# ridicideska.net
KiCad netlist of a schematic drawn in EAGLE
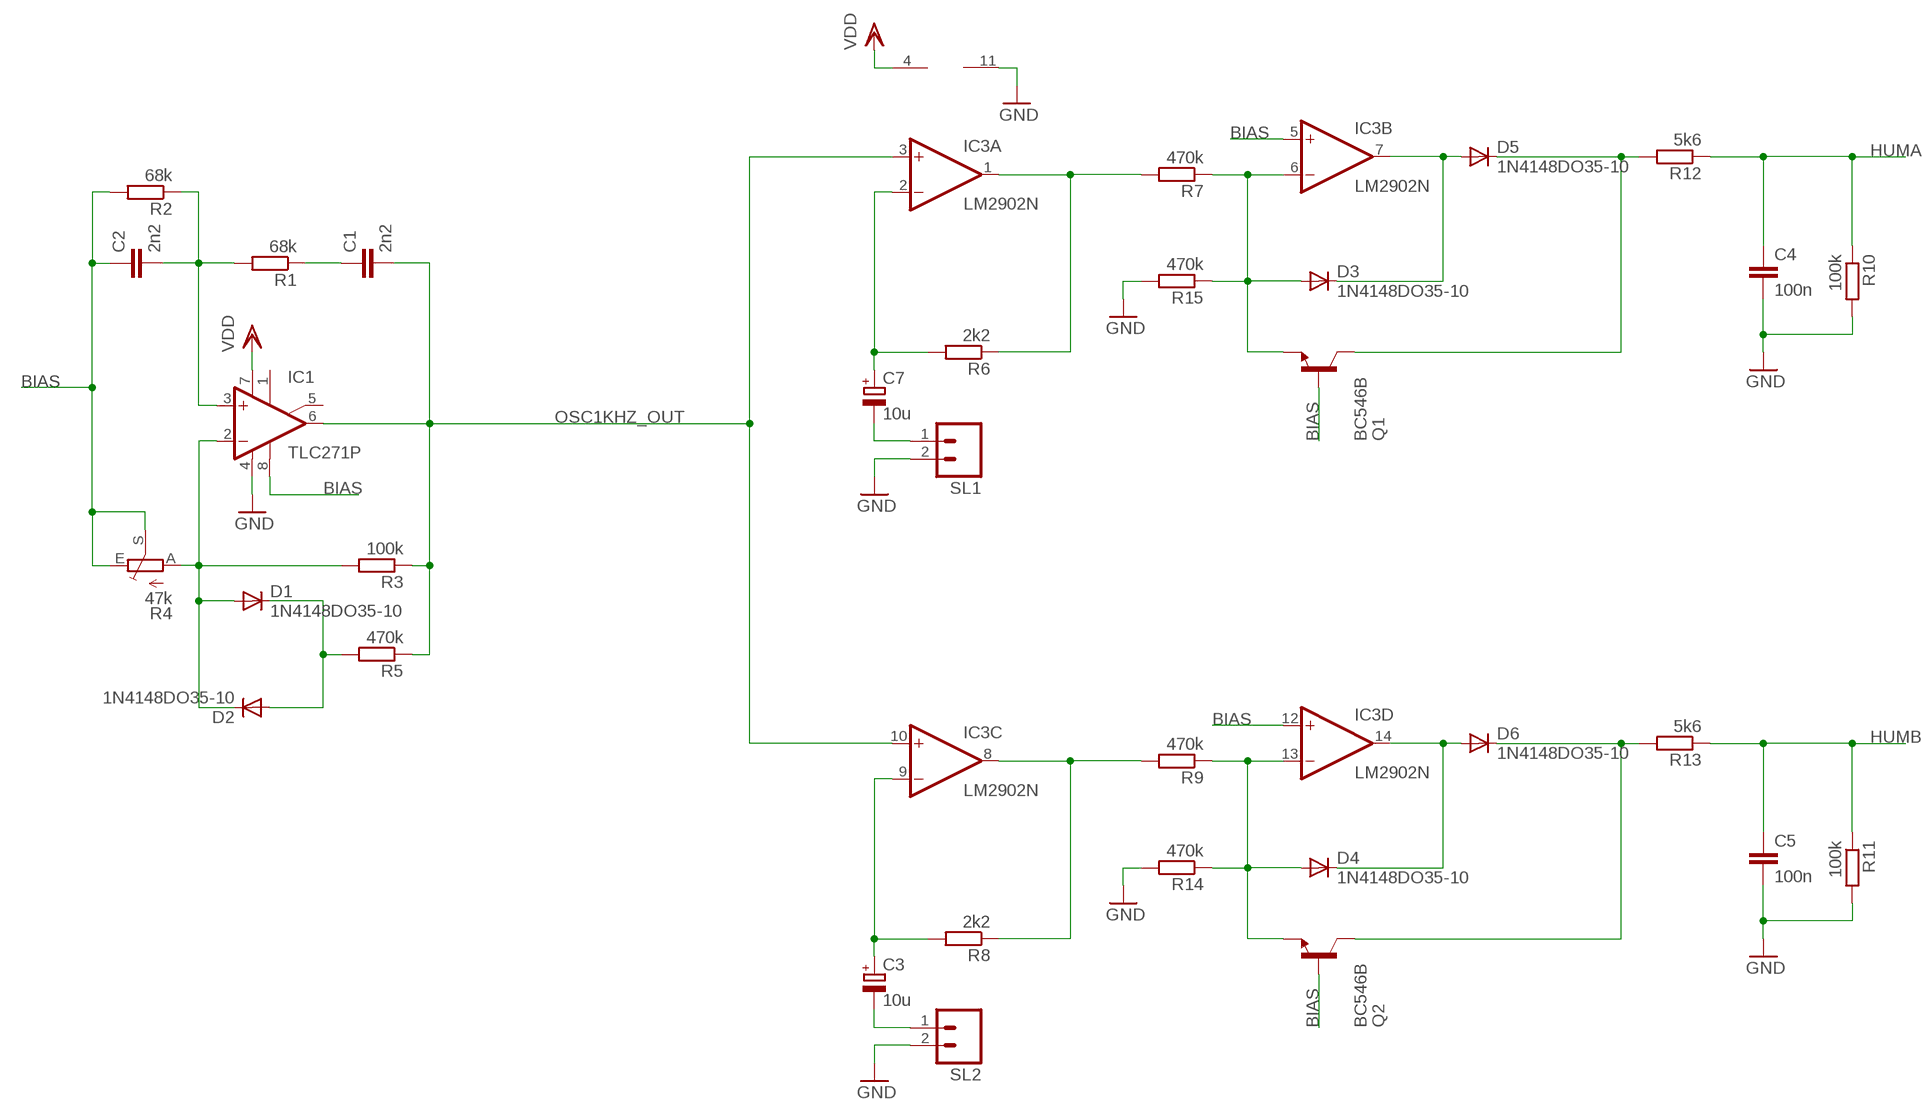
[diagram p0: schematic, sheet 1]
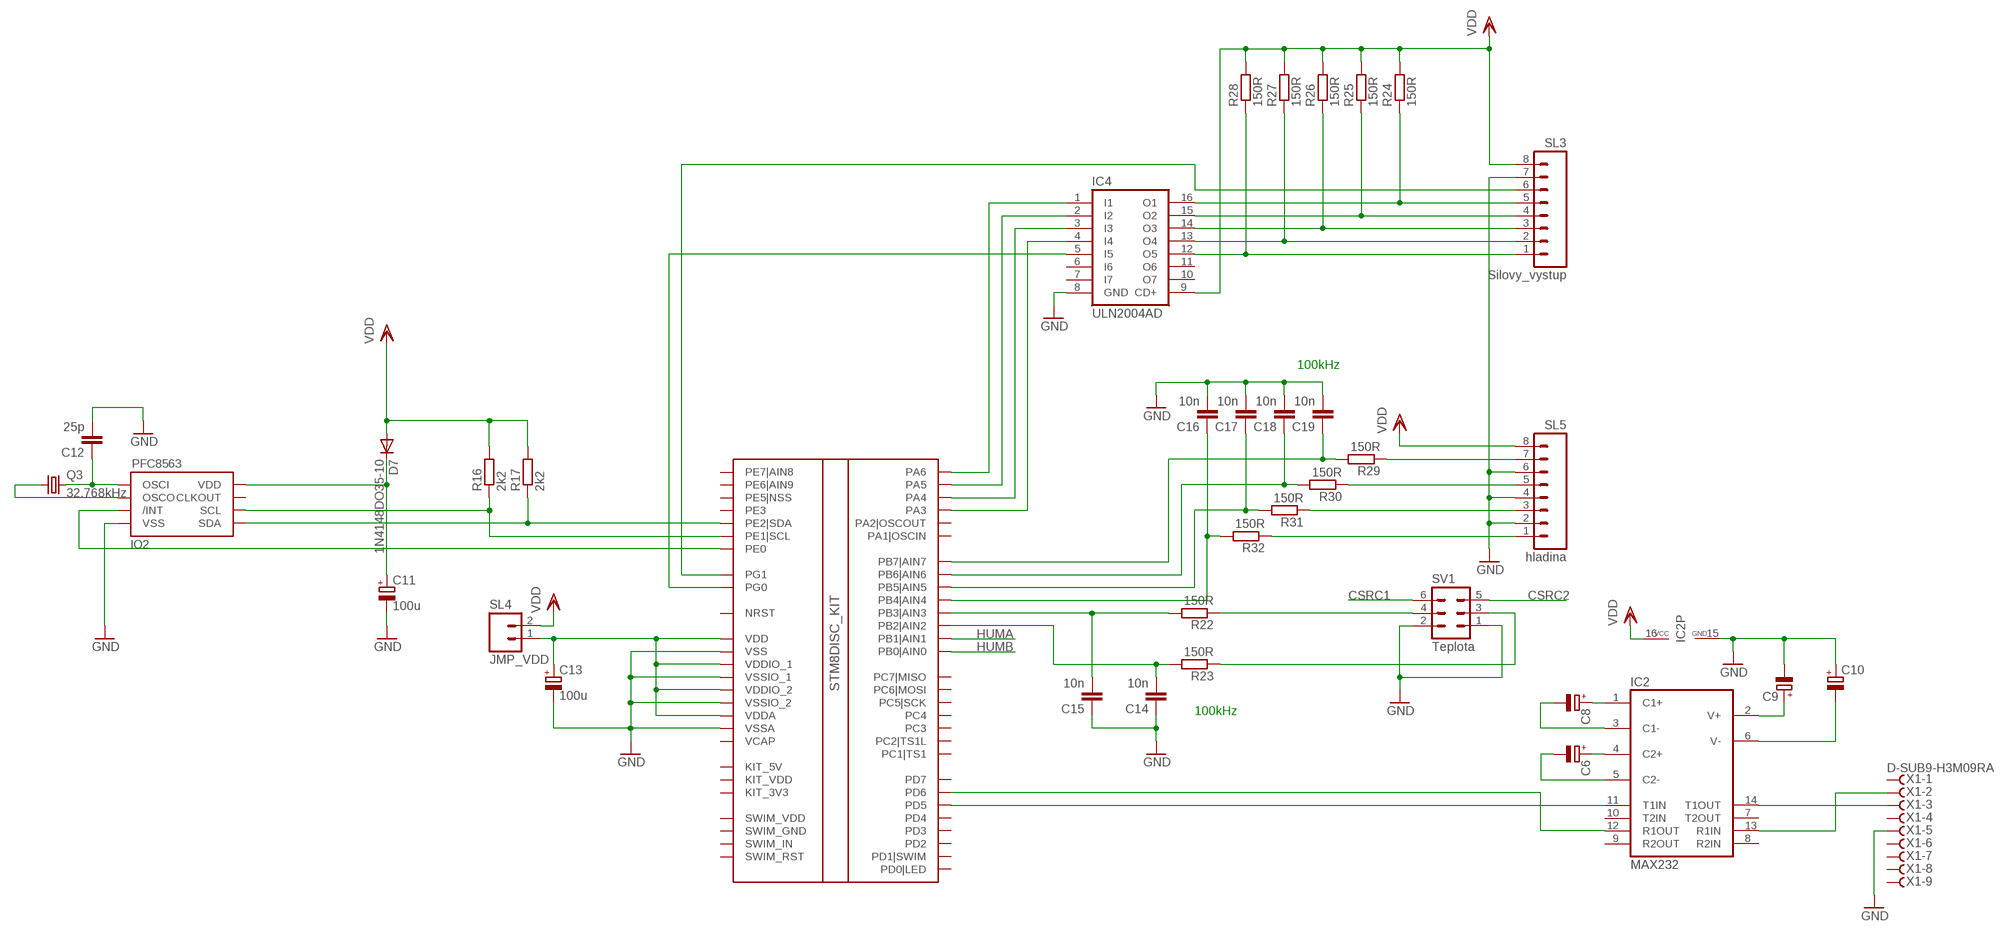
[diagram p1: schematic, sheet 2]
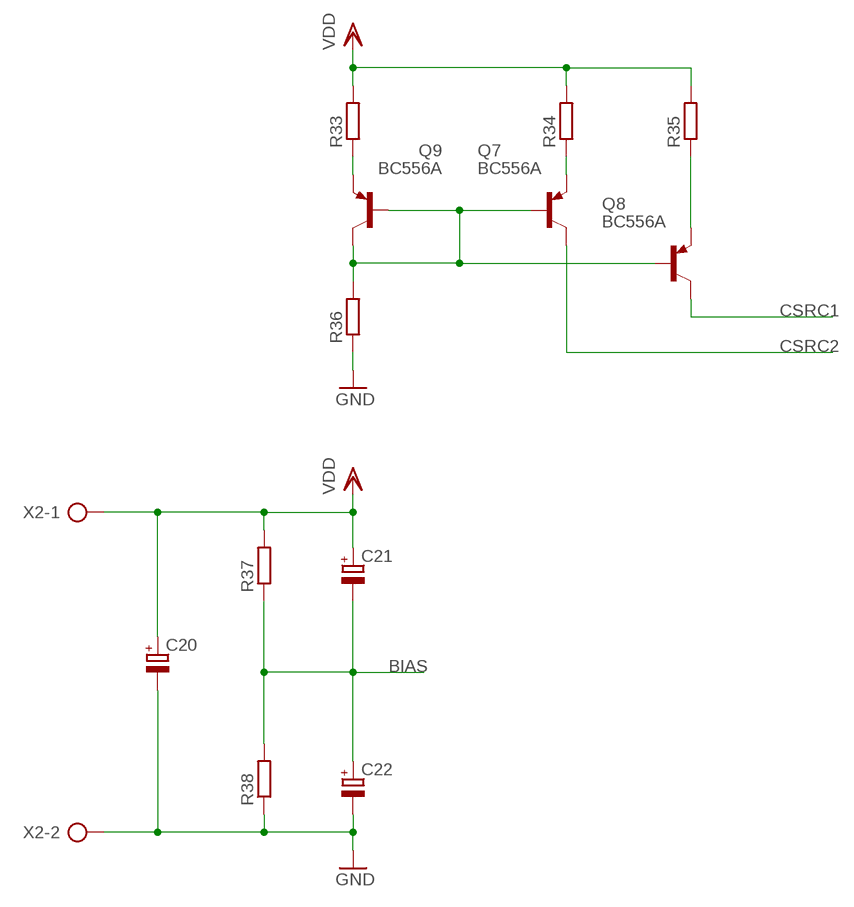
[diagram p2: schematic, sheet 3]

(export (version "E")
  (design (tool "Eeschema 10.0.6"))
  (components
    (comp (ref "C20")
      (value "CPOL-EUE5-10.5")
      (footprint "eagle-import:E5-10,5")
      (libsource (lib "eagle-import") (part "resistor_CPOL-EUE5-10.5"))
    )
    (comp (ref "C21")
      (value "CPOL-EUE5-10.5")
      (footprint "eagle-import:E5-10,5")
      (libsource (lib "eagle-import") (part "resistor_CPOL-EUE5-10.5"))
    )
    (comp (ref "C22")
      (value "CPOL-EUE5-10.5")
      (footprint "eagle-import:E5-10,5")
      (libsource (lib "eagle-import") (part "resistor_CPOL-EUE5-10.5"))
    )
    (comp (ref "Q7")
      (value "BC556A")
      (footprint "eagle-import:TO92-EBC")
      (libsource (lib "eagle-import") (part "BC556A"))
    )
    (comp (ref "Q8")
      (value "BC556A")
      (footprint "eagle-import:TO92-EBC")
      (libsource (lib "eagle-import") (part "BC556A"))
    )
    (comp (ref "Q9")
      (value "BC556A")
      (footprint "eagle-import:TO92-EBC")
      (libsource (lib "eagle-import") (part "BC556A"))
    )
    (comp (ref "R33")
      (value "R-EU_R0805")
      (footprint "eagle-import:R0805")
      (libsource (lib "eagle-import") (part "R-EU_R0805"))
    )
    (comp (ref "R34")
      (value "R-EU_R0805")
      (footprint "eagle-import:R0805")
      (libsource (lib "eagle-import") (part "R-EU_R0805"))
    )
    (comp (ref "R35")
      (value "R-EU_R0805")
      (footprint "eagle-import:R0805")
      (libsource (lib "eagle-import") (part "R-EU_R0805"))
    )
    (comp (ref "R36")
      (value "R-EU_R0805")
      (footprint "eagle-import:R0805")
      (libsource (lib "eagle-import") (part "R-EU_R0805"))
    )
    (comp (ref "R37")
      (value "R-EU_0207/12")
      (footprint "eagle-import:0207_12")
      (libsource (lib "eagle-import") (part "resistor_R-EU_0207/12"))
    )
    (comp (ref "R38")
      (value "R-EU_0207/12")
      (footprint "eagle-import:0207_12")
      (libsource (lib "eagle-import") (part "resistor_R-EU_0207/12"))
    )
    (comp (ref "X2")
      (value "AK300/2")
      (footprint "eagle-import:AK300_2")
      (libsource (lib "eagle-import") (part "AK300/2"))
    )
    (comp (ref "C6")
      (value "CPOL-EUE5-10.5")
      (footprint "eagle-import:E5-10,5")
      (libsource (lib "eagle-import") (part "resistor_CPOL-EUE5-10.5"))
    )
    (comp (ref "C8")
      (value "CPOL-EUE5-10.5")
      (footprint "eagle-import:E5-10,5")
      (libsource (lib "eagle-import") (part "resistor_CPOL-EUE5-10.5"))
    )
    (comp (ref "C9")
      (value "CPOL-EUE5-10.5")
      (footprint "eagle-import:E5-10,5")
      (libsource (lib "eagle-import") (part "resistor_CPOL-EUE5-10.5"))
    )
    (comp (ref "C10")
      (value "CPOL-EUE5-10.5")
      (footprint "eagle-import:E5-10,5")
      (libsource (lib "eagle-import") (part "resistor_CPOL-EUE5-10.5"))
    )
    (comp (ref "C11")
      (value "100u")
      (footprint "eagle-import:E5-10,5")
      (libsource (lib "eagle-import") (part "resistor_CPOL-EUE5-10.5"))
    )
    (comp (ref "C12")
      (value "25p")
      (footprint "eagle-import:C0805")
      (libsource (lib "eagle-import") (part "C-EUC0805"))
    )
    (comp (ref "C13")
      (value "100u")
      (footprint "eagle-import:E5-10,5")
      (libsource (lib "eagle-import") (part "resistor_CPOL-EUE5-10.5"))
    )
    (comp (ref "C14")
      (value "10n")
      (footprint "eagle-import:C0805")
      (libsource (lib "eagle-import") (part "C-EUC0805"))
    )
    (comp (ref "C15")
      (value "10n")
      (footprint "eagle-import:C0805")
      (libsource (lib "eagle-import") (part "C-EUC0805"))
    )
    (comp (ref "C16")
      (value "10n")
      (footprint "eagle-import:C0805")
      (libsource (lib "eagle-import") (part "C-EUC0805"))
    )
    (comp (ref "C17")
      (value "10n")
      (footprint "eagle-import:C0805")
      (libsource (lib "eagle-import") (part "C-EUC0805"))
    )
    (comp (ref "C18")
      (value "10n")
      (footprint "eagle-import:C0805")
      (libsource (lib "eagle-import") (part "C-EUC0805"))
    )
    (comp (ref "C19")
      (value "10n")
      (footprint "eagle-import:C0805")
      (libsource (lib "eagle-import") (part "C-EUC0805"))
    )
    (comp (ref "D7")
      (value "1N4148DO35-10")
      (footprint "eagle-import:DO35-10")
      (libsource (lib "eagle-import") (part "1N4148DO35-10"))
    )
    (comp (ref "IC2")
      (value "MAX232")
      (footprint "eagle-import:DIL16")
      (fields (field (name "MF") "MAXIM") (field (name "MPN") "MAX232ACPE+"))
      (libsource (lib "eagle-import") (part "MAX232"))
    )
    (comp (ref "IC4")
      (value "ULN2004AD")
      (footprint "eagle-import:SO16")
      (libsource (lib "eagle-import") (part "ULN2004AD"))
    )
    (comp (ref "IO1")
      (value "STM8_KIT")
      (footprint "eagle-import:STM8SDISCOVERY")
      (libsource (lib "eagle-import") (part "STM8_KIT"))
    )
    (comp (ref "IO2")
      (value "PFC8563")
      (footprint "eagle-import:SO08")
      (libsource (lib "eagle-import") (part "PFC8563"))
    )
    (comp (ref "Q3")
      (value "32.768kHz")
      (footprint "eagle-import:HC49U70")
      (libsource (lib "eagle-import") (part "CRYSTALHC49U70"))
    )
    (comp (ref "R16")
      (value "2k2")
      (footprint "eagle-import:0207_12")
      (libsource (lib "eagle-import") (part "R-EU_0207/12"))
    )
    (comp (ref "R17")
      (value "2k2")
      (footprint "eagle-import:0207_12")
      (libsource (lib "eagle-import") (part "R-EU_0207/12"))
    )
    (comp (ref "R22")
      (value "150R")
      (footprint "eagle-import:R0805")
      (libsource (lib "eagle-import") (part "R-EU_R0805"))
    )
    (comp (ref "R23")
      (value "150R")
      (footprint "eagle-import:R0805")
      (libsource (lib "eagle-import") (part "R-EU_R0805"))
    )
    (comp (ref "R24")
      (value "150R")
      (footprint "eagle-import:0207_12")
      (libsource (lib "eagle-import") (part "R-EU_0207/12"))
    )
    (comp (ref "R25")
      (value "150R")
      (footprint "eagle-import:0207_12")
      (libsource (lib "eagle-import") (part "R-EU_0207/12"))
    )
    (comp (ref "R26")
      (value "150R")
      (footprint "eagle-import:0207_12")
      (libsource (lib "eagle-import") (part "R-EU_0207/12"))
    )
    (comp (ref "R27")
      (value "150R")
      (footprint "eagle-import:0207_12")
      (libsource (lib "eagle-import") (part "R-EU_0207/12"))
    )
    (comp (ref "R28")
      (value "150R")
      (footprint "eagle-import:0207_12")
      (libsource (lib "eagle-import") (part "R-EU_0207/12"))
    )
    (comp (ref "R29")
      (value "150R")
      (footprint "eagle-import:R0805")
      (libsource (lib "eagle-import") (part "R-EU_R0805"))
    )
    (comp (ref "R30")
      (value "150R")
      (footprint "eagle-import:R0805")
      (libsource (lib "eagle-import") (part "R-EU_R0805"))
    )
    (comp (ref "R31")
      (value "150R")
      (footprint "eagle-import:R0805")
      (libsource (lib "eagle-import") (part "R-EU_R0805"))
    )
    (comp (ref "R32")
      (value "150R")
      (footprint "eagle-import:R0805")
      (libsource (lib "eagle-import") (part "R-EU_R0805"))
    )
    (comp (ref "SL3")
      (value "Silovy_vystup")
      (footprint "eagle-import:08P")
      (libsource (lib "eagle-import") (part "M08"))
    )
    (comp (ref "SL4")
      (value "JMP_VDD")
      (footprint "eagle-import:02P")
      (libsource (lib "eagle-import") (part "M02"))
    )
    (comp (ref "SL5")
      (value "hladina")
      (footprint "eagle-import:08P")
      (fields (field (name "OC_FARNELL") "unknown") (field (name "OC_NEWARK") "unknown"))
      (libsource (lib "eagle-import") (part "M08"))
    )
    (comp (ref "SV1")
      (value "Teplota")
      (footprint "eagle-import:MA03-2")
      (libsource (lib "eagle-import") (part "MA03-2"))
    )
    (comp (ref "X1")
      (value "D-SUB9-H3M09RA")
      (footprint "eagle-import:H3M09RA")
      (libsource (lib "eagle-import") (part "D-SUB9-H3M09RA"))
    )
    (comp (ref "C1")
      (value "2n2")
      (footprint "eagle-import:C0805")
      (libsource (lib "eagle-import") (part "C-EUC0805"))
    )
    (comp (ref "C2")
      (value "2n2")
      (footprint "eagle-import:C0805")
      (libsource (lib "eagle-import") (part "C-EUC0805"))
    )
    (comp (ref "C3")
      (value "10u")
      (footprint "eagle-import:E5-13")
      (libsource (lib "eagle-import") (part "CPOL-EUE5-13"))
    )
    (comp (ref "C4")
      (value "100n")
      (footprint "eagle-import:C0805")
      (libsource (lib "eagle-import") (part "C-EUC0805"))
    )
    (comp (ref "C5")
      (value "100n")
      (footprint "eagle-import:C0805")
      (libsource (lib "eagle-import") (part "C-EUC0805"))
    )
    (comp (ref "C7")
      (value "10u")
      (footprint "eagle-import:E5-13")
      (libsource (lib "eagle-import") (part "CPOL-EUE5-13"))
    )
    (comp (ref "D1")
      (value "1N4148DO35-10")
      (footprint "eagle-import:DO35-10")
      (libsource (lib "eagle-import") (part "1N4148DO35-10"))
    )
    (comp (ref "D2")
      (value "1N4148DO35-10")
      (footprint "eagle-import:DO35-10")
      (libsource (lib "eagle-import") (part "1N4148DO35-10"))
    )
    (comp (ref "D3")
      (value "1N4148DO35-10")
      (footprint "eagle-import:DO35-10")
      (libsource (lib "eagle-import") (part "1N4148DO35-10"))
    )
    (comp (ref "D4")
      (value "1N4148DO35-10")
      (footprint "eagle-import:DO35-10")
      (libsource (lib "eagle-import") (part "1N4148DO35-10"))
    )
    (comp (ref "D5")
      (value "1N4148DO35-10")
      (footprint "eagle-import:DO35-10")
      (libsource (lib "eagle-import") (part "1N4148DO35-10"))
    )
    (comp (ref "D6")
      (value "1N4148DO35-10")
      (footprint "eagle-import:DO35-10")
      (libsource (lib "eagle-import") (part "1N4148DO35-10"))
    )
    (comp (ref "IC1")
      (value "TLC271P")
      (footprint "eagle-import:DIL08")
      (libsource (lib "eagle-import") (part "TLC271P"))
    )
    (comp (ref "IC3")
      (value "LM2902N")
      (footprint "eagle-import:DIL14")
      (libsource (lib "eagle-import") (part "LM2902N"))
    )
    (comp (ref "Q1")
      (value "BC546B")
      (footprint "eagle-import:TO92-EBC")
      (libsource (lib "eagle-import") (part "BC546B"))
    )
    (comp (ref "Q2")
      (value "BC546B")
      (footprint "eagle-import:TO92-EBC")
      (libsource (lib "eagle-import") (part "BC546B"))
    )
    (comp (ref "R1")
      (value "68k")
      (footprint "eagle-import:R0805")
      (libsource (lib "eagle-import") (part "R-EU_R0805"))
    )
    (comp (ref "R2")
      (value "68k")
      (footprint "eagle-import:R0805")
      (libsource (lib "eagle-import") (part "R-EU_R0805"))
    )
    (comp (ref "R3")
      (value "100k")
      (footprint "eagle-import:R0805")
      (libsource (lib "eagle-import") (part "R-EU_R0805"))
    )
    (comp (ref "R4")
      (value "47k")
      (footprint "eagle-import:CA6V")
      (libsource (lib "eagle-import") (part "TRIM_EU-CA6V"))
    )
    (comp (ref "R5")
      (value "470k")
      (footprint "eagle-import:R0805")
      (libsource (lib "eagle-import") (part "R-EU_R0805"))
    )
    (comp (ref "R6")
      (value "2k2")
      (footprint "eagle-import:R0805")
      (libsource (lib "eagle-import") (part "R-EU_R0805"))
    )
    (comp (ref "R7")
      (value "470k")
      (footprint "eagle-import:R0805")
      (libsource (lib "eagle-import") (part "R-EU_R0805"))
    )
    (comp (ref "R8")
      (value "2k2")
      (footprint "eagle-import:R0805")
      (libsource (lib "eagle-import") (part "R-EU_R0805"))
    )
    (comp (ref "R9")
      (value "470k")
      (footprint "eagle-import:R0805")
      (libsource (lib "eagle-import") (part "R-EU_R0805"))
    )
    (comp (ref "R10")
      (value "100k")
      (footprint "eagle-import:R0805")
      (libsource (lib "eagle-import") (part "R-EU_R0805"))
    )
    (comp (ref "R11")
      (value "100k")
      (footprint "eagle-import:R0805")
      (libsource (lib "eagle-import") (part "R-EU_R0805"))
    )
    (comp (ref "R12")
      (value "5k6")
      (footprint "eagle-import:R0805")
      (libsource (lib "eagle-import") (part "R-EU_R0805"))
    )
    (comp (ref "R13")
      (value "5k6")
      (footprint "eagle-import:R0805")
      (libsource (lib "eagle-import") (part "R-EU_R0805"))
    )
    (comp (ref "R14")
      (value "470k")
      (footprint "eagle-import:R0805")
      (libsource (lib "eagle-import") (part "R-EU_R0805"))
    )
    (comp (ref "R15")
      (value "470k")
      (footprint "eagle-import:R0805")
      (libsource (lib "eagle-import") (part "R-EU_R0805"))
    )
    (comp (ref "SL1")
      (value "M02")
      (footprint "eagle-import:02P")
      (libsource (lib "eagle-import") (part "M02"))
    )
    (comp (ref "SL2")
      (value "M02")
      (footprint "eagle-import:02P")
      (libsource (lib "eagle-import") (part "M02"))
    )
  )
  (nets
    (net (code "1") (name "BIAS") (class "Default")
      (node (ref "C2") (pin "1") (pinfunction "1_1") (pintype "passive"))
      (node (ref "C21") (pin "-") (pinfunction "-_-") (pintype "passive"))
      (node (ref "C22") (pin "+") (pinfunction "+_+") (pintype "passive"))
      (node (ref "IC1") (pin "8") (pinfunction "OPT_8") (pintype "passive"))
      (node (ref "IC3") (pin "12") (pinfunction "+IN_12") (pintype "input"))
      (node (ref "IC3") (pin "5") (pinfunction "+IN_5") (pintype "input"))
      (node (ref "Q1") (pin "B") (pinfunction "B_B") (pintype "passive"))
      (node (ref "Q2") (pin "B") (pinfunction "B_B") (pintype "passive"))
      (node (ref "R2") (pin "2") (pinfunction "2_2") (pintype "passive"))
      (node (ref "R37") (pin "1") (pinfunction "1_1") (pintype "passive"))
      (node (ref "R38") (pin "2") (pinfunction "2_2") (pintype "passive"))
      (node (ref "R4") (pin "E") (pinfunction "E_E") (pintype "passive"))
      (node (ref "R4") (pin "S") (pinfunction "S_S") (pintype "passive"))
    )
    (net (code "2") (name "CSRC1") (class "Default")
      (node (ref "Q8") (pin "C") (pinfunction "C_C") (pintype "passive"))
      (node (ref "SV1") (pin "6") (pinfunction "6_6") (pintype "passive"))
    )
    (net (code "3") (name "CSRC2") (class "Default")
      (node (ref "Q7") (pin "C") (pinfunction "C_C") (pintype "passive"))
      (node (ref "SV1") (pin "5") (pinfunction "5_5") (pintype "passive"))
    )
    (net (code "4") (name "GND") (class "Default")
      (node (ref "C10") (pin "+") (pinfunction "+_+") (pintype "passive"))
      (node (ref "C11") (pin "-") (pinfunction "-_-") (pintype "passive"))
      (node (ref "C12") (pin "2") (pinfunction "2_2") (pintype "passive"))
      (node (ref "C13") (pin "-") (pinfunction "-_-") (pintype "passive"))
      (node (ref "C14") (pin "1") (pinfunction "1_1") (pintype "passive"))
      (node (ref "C15") (pin "1") (pinfunction "1_1") (pintype "passive"))
      (node (ref "C16") (pin "2") (pinfunction "2_2") (pintype "passive"))
      (node (ref "C17") (pin "2") (pinfunction "2_2") (pintype "passive"))
      (node (ref "C18") (pin "2") (pinfunction "2_2") (pintype "passive"))
      (node (ref "C19") (pin "2") (pinfunction "2_2") (pintype "passive"))
      (node (ref "C20") (pin "-") (pinfunction "-_-") (pintype "passive"))
      (node (ref "C22") (pin "-") (pinfunction "-_-") (pintype "passive"))
      (node (ref "C4") (pin "2") (pinfunction "2_2") (pintype "passive"))
      (node (ref "C5") (pin "2") (pinfunction "2_2") (pintype "passive"))
      (node (ref "C9") (pin "-") (pinfunction "-_-") (pintype "passive"))
      (node (ref "IC1") (pin "4") (pinfunction "V-_4") (pintype "power_in"))
      (node (ref "IC2") (pin "15") (pinfunction "GND_15") (pintype "power_in"))
      (node (ref "IC3") (pin "11") (pinfunction "V-_11") (pintype "power_in"))
      (node (ref "IC4") (pin "8") (pinfunction "GND_8") (pintype "power_in"))
      (node (ref "IO1") (pin "VSS") (pinfunction "VSS_VSS") (pintype "bidirectional"))
      (node (ref "IO1") (pin "VSSA") (pinfunction "VSSA_VSSA") (pintype "bidirectional"))
      (node (ref "IO1") (pin "VSSIO_1") (pinfunction "VSSIO_1_VSSIO_1") (pintype "bidirectional"))
      (node (ref "IO1") (pin "VSSIO_2") (pinfunction "VSSIO_2_VSSIO_2") (pintype "bidirectional"))
      (node (ref "IO2") (pin "4") (pinfunction "VSS_4") (pintype "bidirectional"))
      (node (ref "R10") (pin "2") (pinfunction "2_2") (pintype "passive"))
      (node (ref "R11") (pin "2") (pinfunction "2_2") (pintype "passive"))
      (node (ref "R14") (pin "2") (pinfunction "2_2") (pintype "passive"))
      (node (ref "R15") (pin "2") (pinfunction "2_2") (pintype "passive"))
      (node (ref "R36") (pin "1") (pinfunction "1_1") (pintype "passive"))
      (node (ref "R38") (pin "1") (pinfunction "1_1") (pintype "passive"))
      (node (ref "SL1") (pin "2") (pinfunction "2_2") (pintype "passive"))
      (node (ref "SL2") (pin "2") (pinfunction "2_2") (pintype "passive"))
      (node (ref "SL3") (pin "7") (pinfunction "7_7") (pintype "passive"))
      (node (ref "SL5") (pin "2") (pinfunction "2_2") (pintype "passive"))
      (node (ref "SL5") (pin "4") (pinfunction "4_4") (pintype "passive"))
      (node (ref "SL5") (pin "6") (pinfunction "6_6") (pintype "passive"))
      (node (ref "SV1") (pin "1") (pinfunction "1_1") (pintype "passive"))
      (node (ref "SV1") (pin "2") (pinfunction "2_2") (pintype "passive"))
      (node (ref "X1") (pin "5") (pinfunction "F_5") (pintype "passive"))
      (node (ref "X2") (pin "2") (pinfunction "KL_2") (pintype "passive"))
    )
    (net (code "5") (name "HUMA") (class "Default")
      (node (ref "C4") (pin "1") (pinfunction "1_1") (pintype "passive"))
      (node (ref "IO1") (pin "PB1") (pinfunction "PB1|AIN1_PB1") (pintype "bidirectional"))
      (node (ref "R10") (pin "1") (pinfunction "1_1") (pintype "passive"))
      (node (ref "R12") (pin "1") (pinfunction "1_1") (pintype "passive"))
    )
    (net (code "6") (name "HUMB") (class "Default")
      (node (ref "C5") (pin "1") (pinfunction "1_1") (pintype "passive"))
      (node (ref "IO1") (pin "PB0") (pinfunction "PB0|AIN0_PB0") (pintype "bidirectional"))
      (node (ref "R11") (pin "1") (pinfunction "1_1") (pintype "passive"))
      (node (ref "R13") (pin "1") (pinfunction "1_1") (pintype "passive"))
    )
    (net (code "7") (name "Net-(C1-Pad1)") (class "Default")
      (node (ref "C1") (pin "1") (pinfunction "1_1") (pintype "passive"))
      (node (ref "R1") (pin "1") (pinfunction "1_1") (pintype "passive"))
    )
    (net (code "8") (name "Net-(C3-Pad-)") (class "Default")
      (node (ref "C3") (pin "-") (pinfunction "-_-") (pintype "passive"))
      (node (ref "SL2") (pin "1") (pinfunction "1_1") (pintype "passive"))
    )
    (net (code "9") (name "Net-(C7-Pad-)") (class "Default")
      (node (ref "C7") (pin "-") (pinfunction "-_-") (pintype "passive"))
      (node (ref "SL1") (pin "1") (pinfunction "1_1") (pintype "passive"))
    )
    (net (code "10") (name "Net-(C13-Pad+)") (class "Default")
      (node (ref "C13") (pin "+") (pinfunction "+_+") (pintype "passive"))
      (node (ref "IO1") (pin "VDD") (pinfunction "VDD_VDD") (pintype "bidirectional"))
      (node (ref "IO1") (pin "VDDA") (pinfunction "VDDA_VDDA") (pintype "bidirectional"))
      (node (ref "IO1") (pin "VDDIO_1") (pinfunction "VDDIO_1_VDDIO_1") (pintype "bidirectional"))
      (node (ref "IO1") (pin "VDDIO_2") (pinfunction "VDDIO_2_VDDIO_2") (pintype "bidirectional"))
      (node (ref "SL4") (pin "1") (pinfunction "1_1") (pintype "passive"))
    )
    (net (code "11") (name "Net-(D1-PadC)") (class "Default")
      (node (ref "D1") (pin "C") (pinfunction "C_C") (pintype "passive"))
      (node (ref "D2") (pin "A") (pinfunction "A_A") (pintype "passive"))
      (node (ref "R5") (pin "2") (pinfunction "2_2") (pintype "passive"))
    )
    (net (code "12") (name "Net-(D5-PadC)") (class "Default")
      (node (ref "D5") (pin "C") (pinfunction "C_C") (pintype "passive"))
      (node (ref "Q1") (pin "C") (pinfunction "C_C") (pintype "passive"))
      (node (ref "R12") (pin "2") (pinfunction "2_2") (pintype "passive"))
    )
    (net (code "13") (name "Net-(D6-PadC)") (class "Default")
      (node (ref "D6") (pin "C") (pinfunction "C_C") (pintype "passive"))
      (node (ref "Q2") (pin "C") (pinfunction "C_C") (pintype "passive"))
      (node (ref "R13") (pin "2") (pinfunction "2_2") (pintype "passive"))
    )
    (net (code "14") (name "Net-(IC1-+IN)") (class "Default")
      (node (ref "C2") (pin "2") (pinfunction "2_2") (pintype "passive"))
      (node (ref "IC1") (pin "3") (pinfunction "+IN_3") (pintype "input"))
      (node (ref "R1") (pin "2") (pinfunction "2_2") (pintype "passive"))
      (node (ref "R2") (pin "1") (pinfunction "1_1") (pintype "passive"))
    )
    (net (code "15") (name "Net-(IC1--IN)") (class "Default")
      (node (ref "D1") (pin "A") (pinfunction "A_A") (pintype "passive"))
      (node (ref "D2") (pin "C") (pinfunction "C_C") (pintype "passive"))
      (node (ref "IC1") (pin "2") (pinfunction "-IN_2") (pintype "input"))
      (node (ref "R3") (pin "2") (pinfunction "2_2") (pintype "passive"))
      (node (ref "R4") (pin "A") (pinfunction "A_A") (pintype "passive"))
    )
    (net (code "16") (name "Net-(IC2A-C1+)") (class "Default")
      (node (ref "C8") (pin "+") (pinfunction "+_+") (pintype "passive"))
      (node (ref "IC2") (pin "1") (pinfunction "C1+_1") (pintype "bidirectional"))
    )
    (net (code "17") (name "Net-(IC2A-C1-)") (class "Default")
      (node (ref "C8") (pin "-") (pinfunction "-_-") (pintype "passive"))
      (node (ref "IC2") (pin "3") (pinfunction "C1-_3") (pintype "bidirectional"))
    )
    (net (code "18") (name "Net-(IC2A-C2+)") (class "Default")
      (node (ref "C6") (pin "+") (pinfunction "+_+") (pintype "passive"))
      (node (ref "IC2") (pin "4") (pinfunction "C2+_4") (pintype "bidirectional"))
    )
    (net (code "19") (name "Net-(IC2A-C2-)") (class "Default")
      (node (ref "C6") (pin "-") (pinfunction "-_-") (pintype "passive"))
      (node (ref "IC2") (pin "5") (pinfunction "C2-_5") (pintype "bidirectional"))
    )
    (net (code "20") (name "Net-(IC2A-R1IN)") (class "Default")
      (node (ref "IC2") (pin "13") (pinfunction "R1IN_13") (pintype "input"))
      (node (ref "X1") (pin "2") (pinfunction "F_2") (pintype "passive"))
    )
    (net (code "21") (name "Net-(IC2A-R1OUT)") (class "Default")
      (node (ref "IC2") (pin "12") (pinfunction "R1OUT_12") (pintype "output"))
      (node (ref "IO1") (pin "PD6") (pinfunction "PD6_PD6") (pintype "bidirectional"))
    )
    (net (code "22") (name "Net-(IC2A-T1IN)") (class "Default")
      (node (ref "IC2") (pin "11") (pinfunction "T1IN_11") (pintype "input"))
      (node (ref "IO1") (pin "PD5") (pinfunction "PD5_PD5") (pintype "bidirectional"))
    )
    (net (code "23") (name "Net-(IC2A-T1OUT)") (class "Default")
      (node (ref "IC2") (pin "14") (pinfunction "T1OUT_14") (pintype "output"))
      (node (ref "X1") (pin "3") (pinfunction "F_3") (pintype "passive"))
    )
    (net (code "24") (name "Net-(IC2A-V+)") (class "Default")
      (node (ref "C9") (pin "+") (pinfunction "+_+") (pintype "passive"))
      (node (ref "IC2") (pin "2") (pinfunction "V+_2") (pintype "bidirectional"))
    )
    (net (code "25") (name "Net-(IC2A-V-)") (class "Default")
      (node (ref "C10") (pin "-") (pinfunction "-_-") (pintype "passive"))
      (node (ref "IC2") (pin "6") (pinfunction "V-_6") (pintype "bidirectional"))
    )
    (net (code "26") (name "Net-(IC3A--IN)") (class "Default")
      (node (ref "C7") (pin "+") (pinfunction "+_+") (pintype "passive"))
      (node (ref "IC3") (pin "2") (pinfunction "-IN_2") (pintype "input"))
      (node (ref "R6") (pin "2") (pinfunction "2_2") (pintype "passive"))
    )
    (net (code "27") (name "Net-(IC3A-OUT)") (class "Default")
      (node (ref "IC3") (pin "1") (pinfunction "OUT_1") (pintype "output"))
      (node (ref "R6") (pin "1") (pinfunction "1_1") (pintype "passive"))
      (node (ref "R7") (pin "2") (pinfunction "2_2") (pintype "passive"))
    )
    (net (code "28") (name "Net-(IC3B--IN)") (class "Default")
      (node (ref "D3") (pin "A") (pinfunction "A_A") (pintype "passive"))
      (node (ref "IC3") (pin "6") (pinfunction "-IN_6") (pintype "input"))
      (node (ref "Q1") (pin "E") (pinfunction "E_E") (pintype "passive"))
      (node (ref "R15") (pin "1") (pinfunction "1_1") (pintype "passive"))
      (node (ref "R7") (pin "1") (pinfunction "1_1") (pintype "passive"))
    )
    (net (code "29") (name "Net-(IC3B-OUT)") (class "Default")
      (node (ref "D3") (pin "C") (pinfunction "C_C") (pintype "passive"))
      (node (ref "D5") (pin "A") (pinfunction "A_A") (pintype "passive"))
      (node (ref "IC3") (pin "7") (pinfunction "OUT_7") (pintype "output"))
    )
    (net (code "30") (name "Net-(IC3C--IN)") (class "Default")
      (node (ref "C3") (pin "+") (pinfunction "+_+") (pintype "passive"))
      (node (ref "IC3") (pin "9") (pinfunction "-IN_9") (pintype "input"))
      (node (ref "R8") (pin "2") (pinfunction "2_2") (pintype "passive"))
    )
    (net (code "31") (name "Net-(IC3C-OUT)") (class "Default")
      (node (ref "IC3") (pin "8") (pinfunction "OUT_8") (pintype "output"))
      (node (ref "R8") (pin "1") (pinfunction "1_1") (pintype "passive"))
      (node (ref "R9") (pin "2") (pinfunction "2_2") (pintype "passive"))
    )
    (net (code "32") (name "Net-(IC3D--IN)") (class "Default")
      (node (ref "D4") (pin "A") (pinfunction "A_A") (pintype "passive"))
      (node (ref "IC3") (pin "13") (pinfunction "-IN_13") (pintype "input"))
      (node (ref "Q2") (pin "E") (pinfunction "E_E") (pintype "passive"))
      (node (ref "R14") (pin "1") (pinfunction "1_1") (pintype "passive"))
      (node (ref "R9") (pin "1") (pinfunction "1_1") (pintype "passive"))
    )
    (net (code "33") (name "Net-(IC3D-OUT)") (class "Default")
      (node (ref "D4") (pin "C") (pinfunction "C_C") (pintype "passive"))
      (node (ref "D6") (pin "A") (pinfunction "A_A") (pintype "passive"))
      (node (ref "IC3") (pin "14") (pinfunction "OUT_14") (pintype "output"))
    )
    (net (code "34") (name "Net-(IC4-I1)") (class "Default")
      (node (ref "IC4") (pin "1") (pinfunction "I1_1") (pintype "input"))
      (node (ref "IO1") (pin "PA6") (pinfunction "PA6_PA6") (pintype "bidirectional"))
    )
    (net (code "35") (name "Net-(IC4-I2)") (class "Default")
      (node (ref "IC4") (pin "2") (pinfunction "I2_2") (pintype "input"))
      (node (ref "IO1") (pin "PA5") (pinfunction "PA5_PA5") (pintype "bidirectional"))
    )
    (net (code "36") (name "Net-(IC4-I3)") (class "Default")
      (node (ref "IC4") (pin "3") (pinfunction "I3_3") (pintype "input"))
      (node (ref "IO1") (pin "PA4") (pinfunction "PA4_PA4") (pintype "bidirectional"))
    )
    (net (code "37") (name "Net-(IC4-I4)") (class "Default")
      (node (ref "IC4") (pin "4") (pinfunction "I4_4") (pintype "input"))
      (node (ref "IO1") (pin "PA3") (pinfunction "PA3_PA3") (pintype "bidirectional"))
    )
    (net (code "38") (name "Net-(IC4-I5)") (class "Default")
      (node (ref "IC4") (pin "5") (pinfunction "I5_5") (pintype "input"))
      (node (ref "IO1") (pin "PG0") (pinfunction "PG0_PG0") (pintype "bidirectional"))
    )
    (net (code "39") (name "Net-(IC4-O1)") (class "Default")
      (node (ref "IC4") (pin "16") (pinfunction "O1_16") (pintype "open_collector"))
      (node (ref "R24") (pin "1") (pinfunction "1_1") (pintype "passive"))
      (node (ref "SL3") (pin "5") (pinfunction "5_5") (pintype "passive"))
    )
    (net (code "40") (name "Net-(IC4-O2)") (class "Default")
      (node (ref "IC4") (pin "15") (pinfunction "O2_15") (pintype "open_collector"))
      (node (ref "R25") (pin "1") (pinfunction "1_1") (pintype "passive"))
      (node (ref "SL3") (pin "4") (pinfunction "4_4") (pintype "passive"))
    )
    (net (code "41") (name "Net-(IC4-O3)") (class "Default")
      (node (ref "IC4") (pin "14") (pinfunction "O3_14") (pintype "open_collector"))
      (node (ref "R26") (pin "1") (pinfunction "1_1") (pintype "passive"))
      (node (ref "SL3") (pin "3") (pinfunction "3_3") (pintype "passive"))
    )
    (net (code "42") (name "Net-(IC4-O4)") (class "Default")
      (node (ref "IC4") (pin "13") (pinfunction "O4_13") (pintype "open_collector"))
      (node (ref "R27") (pin "1") (pinfunction "1_1") (pintype "passive"))
      (node (ref "SL3") (pin "2") (pinfunction "2_2") (pintype "passive"))
    )
    (net (code "43") (name "Net-(IC4-O5)") (class "Default")
      (node (ref "IC4") (pin "12") (pinfunction "O5_12") (pintype "open_collector"))
      (node (ref "R28") (pin "1") (pinfunction "1_1") (pintype "passive"))
      (node (ref "SL3") (pin "1") (pinfunction "1_1") (pintype "passive"))
    )
    (net (code "44") (name "Net-(IO1-PB2|AIN2)") (class "Default")
      (node (ref "C14") (pin "2") (pinfunction "2_2") (pintype "passive"))
      (node (ref "IO1") (pin "PB2") (pinfunction "PB2|AIN2_PB2") (pintype "bidirectional"))
      (node (ref "R23") (pin "2") (pinfunction "2_2") (pintype "passive"))
    )
    (net (code "45") (name "Net-(IO1-PB3|AIN3)") (class "Default")
      (node (ref "C15") (pin "2") (pinfunction "2_2") (pintype "passive"))
      (node (ref "IO1") (pin "PB3") (pinfunction "PB3|AIN3_PB3") (pintype "bidirectional"))
      (node (ref "R22") (pin "2") (pinfunction "2_2") (pintype "passive"))
    )
    (net (code "46") (name "Net-(IO1-PB4|AIN4)") (class "Default")
      (node (ref "C16") (pin "1") (pinfunction "1_1") (pintype "passive"))
      (node (ref "IO1") (pin "PB4") (pinfunction "PB4|AIN4_PB4") (pintype "bidirectional"))
      (node (ref "R32") (pin "2") (pinfunction "2_2") (pintype "passive"))
    )
    (net (code "47") (name "Net-(IO1-PB5|AIN5)") (class "Default")
      (node (ref "C17") (pin "1") (pinfunction "1_1") (pintype "passive"))
      (node (ref "IO1") (pin "PB5") (pinfunction "PB5|AIN5_PB5") (pintype "bidirectional"))
      (node (ref "R31") (pin "2") (pinfunction "2_2") (pintype "passive"))
    )
    (net (code "48") (name "Net-(IO1-PB6|AIN6)") (class "Default")
      (node (ref "C18") (pin "1") (pinfunction "1_1") (pintype "passive"))
      (node (ref "IO1") (pin "PB6") (pinfunction "PB6|AIN6_PB6") (pintype "bidirectional"))
      (node (ref "R30") (pin "2") (pinfunction "2_2") (pintype "passive"))
    )
    (net (code "49") (name "Net-(IO1-PB7|AIN7)") (class "Default")
      (node (ref "C19") (pin "1") (pinfunction "1_1") (pintype "passive"))
      (node (ref "IO1") (pin "PB7") (pinfunction "PB7|AIN7_PB7") (pintype "bidirectional"))
      (node (ref "R29") (pin "2") (pinfunction "2_2") (pintype "passive"))
    )
    (net (code "50") (name "Net-(IO1-PE1|SCL)") (class "Default")
      (node (ref "IO1") (pin "PE1") (pinfunction "PE1|SCL_PE1") (pintype "bidirectional"))
      (node (ref "IO2") (pin "6") (pinfunction "SCL_6") (pintype "bidirectional"))
      (node (ref "R16") (pin "1") (pinfunction "1_1") (pintype "passive"))
    )
    (net (code "51") (name "Net-(IO1-PE2|SDA)") (class "Default")
      (node (ref "IO1") (pin "PE2") (pinfunction "PE2|SDA_PE2") (pintype "bidirectional"))
      (node (ref "IO2") (pin "5") (pinfunction "SDA_5") (pintype "bidirectional"))
      (node (ref "R17") (pin "1") (pinfunction "1_1") (pintype "passive"))
    )
    (net (code "52") (name "Net-(IO1-PadPG1)") (class "Default")
      (node (ref "IO1") (pin "PG1") (pinfunction "PG1_PG1") (pintype "bidirectional"))
      (node (ref "SL3") (pin "6") (pinfunction "6_6") (pintype "passive"))
    )
    (net (code "53") (name "Net-(IO2-OSCI)") (class "Default")
      (node (ref "C12") (pin "1") (pinfunction "1_1") (pintype "passive"))
      (node (ref "IO2") (pin "1") (pinfunction "OSCI_1") (pintype "bidirectional"))
      (node (ref "Q3") (pin "2") (pinfunction "2_2") (pintype "passive"))
    )
    (net (code "54") (name "Net-(IO2-OSCO)") (class "Default")
      (node (ref "IO2") (pin "2") (pinfunction "OSCO_2") (pintype "bidirectional"))
      (node (ref "Q3") (pin "1") (pinfunction "1_1") (pintype "passive"))
    )
    (net (code "55") (name "Net-(IO2-VDD)") (class "Default")
      (node (ref "C11") (pin "+") (pinfunction "+_+") (pintype "passive"))
      (node (ref "D7") (pin "C") (pinfunction "C_C") (pintype "passive"))
      (node (ref "IO2") (pin "8") (pinfunction "VDD_8") (pintype "bidirectional"))
    )
    (net (code "56") (name "Net-(IO2-{slash}INT)") (class "Default")
      (node (ref "IO1") (pin "PE0") (pinfunction "PE0_PE0") (pintype "bidirectional"))
      (node (ref "IO2") (pin "3") (pinfunction "/INT_3") (pintype "bidirectional"))
    )
    (net (code "57") (name "Net-(Q7-PadB)") (class "Default")
      (node (ref "Q7") (pin "B") (pinfunction "B_B") (pintype "passive"))
      (node (ref "Q8") (pin "B") (pinfunction "B_B") (pintype "passive"))
      (node (ref "Q9") (pin "B") (pinfunction "B_B") (pintype "passive"))
      (node (ref "Q9") (pin "C") (pinfunction "C_C") (pintype "passive"))
      (node (ref "R36") (pin "2") (pinfunction "2_2") (pintype "passive"))
    )
    (net (code "58") (name "Net-(Q7-PadE)") (class "Default")
      (node (ref "Q7") (pin "E") (pinfunction "E_E") (pintype "passive"))
      (node (ref "R34") (pin "1") (pinfunction "1_1") (pintype "passive"))
    )
    (net (code "59") (name "Net-(Q8-PadE)") (class "Default")
      (node (ref "Q8") (pin "E") (pinfunction "E_E") (pintype "passive"))
      (node (ref "R35") (pin "1") (pinfunction "1_1") (pintype "passive"))
    )
    (net (code "60") (name "Net-(Q9-PadE)") (class "Default")
      (node (ref "Q9") (pin "E") (pinfunction "E_E") (pintype "passive"))
      (node (ref "R33") (pin "1") (pinfunction "1_1") (pintype "passive"))
    )
    (net (code "61") (name "Net-(R22-Pad1)") (class "Default")
      (node (ref "R22") (pin "1") (pinfunction "1_1") (pintype "passive"))
      (node (ref "SV1") (pin "4") (pinfunction "4_4") (pintype "passive"))
    )
    (net (code "62") (name "Net-(R23-Pad1)") (class "Default")
      (node (ref "R23") (pin "1") (pinfunction "1_1") (pintype "passive"))
      (node (ref "SV1") (pin "3") (pinfunction "3_3") (pintype "passive"))
    )
    (net (code "63") (name "Net-(R29-Pad1)") (class "Default")
      (node (ref "R29") (pin "1") (pinfunction "1_1") (pintype "passive"))
      (node (ref "SL5") (pin "7") (pinfunction "7_7") (pintype "passive"))
    )
    (net (code "64") (name "Net-(R30-Pad1)") (class "Default")
      (node (ref "R30") (pin "1") (pinfunction "1_1") (pintype "passive"))
      (node (ref "SL5") (pin "5") (pinfunction "5_5") (pintype "passive"))
    )
    (net (code "65") (name "Net-(R31-Pad1)") (class "Default")
      (node (ref "R31") (pin "1") (pinfunction "1_1") (pintype "passive"))
      (node (ref "SL5") (pin "3") (pinfunction "3_3") (pintype "passive"))
    )
    (net (code "66") (name "Net-(R32-Pad1)") (class "Default")
      (node (ref "R32") (pin "1") (pinfunction "1_1") (pintype "passive"))
      (node (ref "SL5") (pin "1") (pinfunction "1_1") (pintype "passive"))
    )
    (net (code "67") (name "OSC1KHZ_OUT") (class "Default")
      (node (ref "C1") (pin "2") (pinfunction "2_2") (pintype "passive"))
      (node (ref "IC1") (pin "6") (pinfunction "OUT_6") (pintype "output"))
      (node (ref "IC3") (pin "10") (pinfunction "+IN_10") (pintype "input"))
      (node (ref "IC3") (pin "3") (pinfunction "+IN_3") (pintype "input"))
      (node (ref "R3") (pin "1") (pinfunction "1_1") (pintype "passive"))
      (node (ref "R5") (pin "1") (pinfunction "1_1") (pintype "passive"))
    )
    (net (code "68") (name "VDD") (class "Default")
      (node (ref "C20") (pin "+") (pinfunction "+_+") (pintype "passive"))
      (node (ref "C21") (pin "+") (pinfunction "+_+") (pintype "passive"))
      (node (ref "D7") (pin "A") (pinfunction "A_A") (pintype "passive"))
      (node (ref "IC1") (pin "7") (pinfunction "V+_7") (pintype "power_in"))
      (node (ref "IC2") (pin "16") (pinfunction "VCC_16") (pintype "power_in"))
      (node (ref "IC3") (pin "4") (pinfunction "V+_4") (pintype "power_in"))
      (node (ref "IC4") (pin "9") (pinfunction "CD+_9") (pintype "passive"))
      (node (ref "R16") (pin "2") (pinfunction "2_2") (pintype "passive"))
      (node (ref "R17") (pin "2") (pinfunction "2_2") (pintype "passive"))
      (node (ref "R24") (pin "2") (pinfunction "2_2") (pintype "passive"))
      (node (ref "R25") (pin "2") (pinfunction "2_2") (pintype "passive"))
      (node (ref "R26") (pin "2") (pinfunction "2_2") (pintype "passive"))
      (node (ref "R27") (pin "2") (pinfunction "2_2") (pintype "passive"))
      (node (ref "R28") (pin "2") (pinfunction "2_2") (pintype "passive"))
      (node (ref "R33") (pin "2") (pinfunction "2_2") (pintype "passive"))
      (node (ref "R34") (pin "2") (pinfunction "2_2") (pintype "passive"))
      (node (ref "R35") (pin "2") (pinfunction "2_2") (pintype "passive"))
      (node (ref "R37") (pin "2") (pinfunction "2_2") (pintype "passive"))
      (node (ref "SL3") (pin "8") (pinfunction "8_8") (pintype "passive"))
      (node (ref "SL4") (pin "2") (pinfunction "2_2") (pintype "passive"))
      (node (ref "SL5") (pin "8") (pinfunction "8_8") (pintype "passive"))
      (node (ref "X2") (pin "1") (pinfunction "KL_1") (pintype "passive"))
    )
    (net (code "69") (name "unconnected-(IC1-ON1-Pad1)") (class "Default")
      (node (ref "IC1") (pin "1") (pinfunction "ON1_1") (pintype "passive"))
    )
    (net (code "70") (name "unconnected-(IC1-ON2-Pad5)") (class "Default")
      (node (ref "IC1") (pin "5") (pinfunction "ON2_5") (pintype "passive"))
    )
    (net (code "71") (name "unconnected-(IC2A-R2IN-Pad8)") (class "Default")
      (node (ref "IC2") (pin "8") (pinfunction "R2IN_8") (pintype "input"))
    )
    (net (code "72") (name "unconnected-(IC2A-R2OUT-Pad9)") (class "Default")
      (node (ref "IC2") (pin "9") (pinfunction "R2OUT_9") (pintype "output"))
    )
    (net (code "73") (name "unconnected-(IC2A-T2IN-Pad10)") (class "Default")
      (node (ref "IC2") (pin "10") (pinfunction "T2IN_10") (pintype "input"))
    )
    (net (code "74") (name "unconnected-(IC2A-T2OUT-Pad7)") (class "Default")
      (node (ref "IC2") (pin "7") (pinfunction "T2OUT_7") (pintype "output"))
    )
    (net (code "75") (name "unconnected-(IC4-I6-Pad6)") (class "Default")
      (node (ref "IC4") (pin "6") (pinfunction "I6_6") (pintype "input"))
    )
    (net (code "76") (name "unconnected-(IC4-I7-Pad7)") (class "Default")
      (node (ref "IC4") (pin "7") (pinfunction "I7_7") (pintype "input"))
    )
    (net (code "77") (name "unconnected-(IC4-O6-Pad11)") (class "Default")
      (node (ref "IC4") (pin "11") (pinfunction "O6_11") (pintype "open_collector"))
    )
    (net (code "78") (name "unconnected-(IC4-O7-Pad10)") (class "Default")
      (node (ref "IC4") (pin "10") (pinfunction "O7_10") (pintype "open_collector"))
    )
    (net (code "79") (name "unconnected-(IO1-PA1|OSCIN-PadPA1)") (class "Default")
      (node (ref "IO1") (pin "PA1") (pinfunction "PA1|OSCIN_PA1") (pintype "bidirectional"))
    )
    (net (code "80") (name "unconnected-(IO1-PA2|OSCOUT-PadPA2)") (class "Default")
      (node (ref "IO1") (pin "PA2") (pinfunction "PA2|OSCOUT_PA2") (pintype "bidirectional"))
    )
    (net (code "81") (name "unconnected-(IO1-PC1|TS1-PadPC1)") (class "Default")
      (node (ref "IO1") (pin "PC1") (pinfunction "PC1|TS1_PC1") (pintype "bidirectional"))
    )
    (net (code "82") (name "unconnected-(IO1-PC2|TS1L-PadPC2)") (class "Default")
      (node (ref "IO1") (pin "PC2") (pinfunction "PC2|TS1L_PC2") (pintype "bidirectional"))
    )
    (net (code "83") (name "unconnected-(IO1-PC5|SCK-PadPC5)") (class "Default")
      (node (ref "IO1") (pin "PC5") (pinfunction "PC5|SCK_PC5") (pintype "bidirectional"))
    )
    (net (code "84") (name "unconnected-(IO1-PC6|MOSI-PadPC6)") (class "Default")
      (node (ref "IO1") (pin "PC6") (pinfunction "PC6|MOSI_PC6") (pintype "bidirectional"))
    )
    (net (code "85") (name "unconnected-(IO1-PC7|MISO-PadPC7)") (class "Default")
      (node (ref "IO1") (pin "PC7") (pinfunction "PC7|MISO_PC7") (pintype "bidirectional"))
    )
    (net (code "86") (name "unconnected-(IO1-PD0|LED-PadPD0)") (class "Default")
      (node (ref "IO1") (pin "PD0") (pinfunction "PD0|LED_PD0") (pintype "bidirectional"))
    )
    (net (code "87") (name "unconnected-(IO1-PD1|SWIM-PadPD1)") (class "Default")
      (node (ref "IO1") (pin "PD1") (pinfunction "PD1|SWIM_PD1") (pintype "bidirectional"))
    )
    (net (code "88") (name "unconnected-(IO1-PE5|NSS-PadPE5)") (class "Default")
      (node (ref "IO1") (pin "PE5") (pinfunction "PE5|NSS_PE5") (pintype "bidirectional"))
    )
    (net (code "89") (name "unconnected-(IO1-PE6|AIN9-PadPE6)") (class "Default")
      (node (ref "IO1") (pin "PE6") (pinfunction "PE6|AIN9_PE6") (pintype "bidirectional"))
    )
    (net (code "90") (name "unconnected-(IO1-PE7|AIN8-PadPE7)") (class "Default")
      (node (ref "IO1") (pin "PE7") (pinfunction "PE7|AIN8_PE7") (pintype "bidirectional"))
    )
    (net (code "91") (name "unconnected-(IO1-PadKIT_3V3)") (class "Default")
      (node (ref "IO1") (pin "KIT_3V3") (pinfunction "KIT_3V3_KIT_3V3") (pintype "bidirectional"))
    )
    (net (code "92") (name "unconnected-(IO1-PadKIT_5V)") (class "Default")
      (node (ref "IO1") (pin "KIT_5V") (pinfunction "KIT_5V_KIT_5V") (pintype "bidirectional"))
    )
    (net (code "93") (name "unconnected-(IO1-PadKIT_VDD)") (class "Default")
      (node (ref "IO1") (pin "KIT_VDD") (pinfunction "KIT_VDD_KIT_VDD") (pintype "bidirectional"))
    )
    (net (code "94") (name "unconnected-(IO1-PadNRST)") (class "Default")
      (node (ref "IO1") (pin "NRST") (pinfunction "NRST_NRST") (pintype "bidirectional"))
    )
    (net (code "95") (name "unconnected-(IO1-PadPC3)") (class "Default")
      (node (ref "IO1") (pin "PC3") (pinfunction "PC3_PC3") (pintype "bidirectional"))
    )
    (net (code "96") (name "unconnected-(IO1-PadPC4)") (class "Default")
      (node (ref "IO1") (pin "PC4") (pinfunction "PC4_PC4") (pintype "bidirectional"))
    )
    (net (code "97") (name "unconnected-(IO1-PadPD2)") (class "Default")
      (node (ref "IO1") (pin "PD2") (pinfunction "PD2_PD2") (pintype "bidirectional"))
    )
    (net (code "98") (name "unconnected-(IO1-PadPD3)") (class "Default")
      (node (ref "IO1") (pin "PD3") (pinfunction "PD3_PD3") (pintype "bidirectional"))
    )
    (net (code "99") (name "unconnected-(IO1-PadPD4)") (class "Default")
      (node (ref "IO1") (pin "PD4") (pinfunction "PD4_PD4") (pintype "bidirectional"))
    )
    (net (code "100") (name "unconnected-(IO1-PadPD7)") (class "Default")
      (node (ref "IO1") (pin "PD7") (pinfunction "PD7_PD7") (pintype "bidirectional"))
    )
    (net (code "101") (name "unconnected-(IO1-PadPE3)") (class "Default")
      (node (ref "IO1") (pin "PE3") (pinfunction "PE3_PE3") (pintype "bidirectional"))
    )
    (net (code "102") (name "unconnected-(IO1-PadSWIM_GND)") (class "Default")
      (node (ref "IO1") (pin "SWIM_GND") (pinfunction "SWIM_GND_SWIM_GND") (pintype "bidirectional"))
    )
    (net (code "103") (name "unconnected-(IO1-PadSWIM_IN)") (class "Default")
      (node (ref "IO1") (pin "SWIM_IN") (pinfunction "SWIM_IN_SWIM_IN") (pintype "bidirectional"))
    )
    (net (code "104") (name "unconnected-(IO1-PadSWIM_RST)") (class "Default")
      (node (ref "IO1") (pin "SWIM_RST") (pinfunction "SWIM_RST_SWIM_RST") (pintype "bidirectional"))
    )
    (net (code "105") (name "unconnected-(IO1-PadSWIM_VDD)") (class "Default")
      (node (ref "IO1") (pin "SWIM_VDD") (pinfunction "SWIM_VDD_SWIM_VDD") (pintype "bidirectional"))
    )
    (net (code "106") (name "unconnected-(IO1-PadVCAP)") (class "Default")
      (node (ref "IO1") (pin "VCAP") (pinfunction "VCAP_VCAP") (pintype "bidirectional"))
    )
    (net (code "107") (name "unconnected-(IO2-CLKOUT-Pad7)") (class "Default")
      (node (ref "IO2") (pin "7") (pinfunction "CLKOUT_7") (pintype "bidirectional"))
    )
    (net (code "108") (name "unconnected-(X1A-F-Pad1)") (class "Default")
      (node (ref "X1") (pin "1") (pinfunction "F_1") (pintype "passive"))
    )
    (net (code "109") (name "unconnected-(X1D-F-Pad4)") (class "Default")
      (node (ref "X1") (pin "4") (pinfunction "F_4") (pintype "passive"))
    )
    (net (code "110") (name "unconnected-(X1F-F-Pad6)") (class "Default")
      (node (ref "X1") (pin "6") (pinfunction "F_6") (pintype "passive"))
    )
    (net (code "111") (name "unconnected-(X1G-F-Pad7)") (class "Default")
      (node (ref "X1") (pin "7") (pinfunction "F_7") (pintype "passive"))
    )
    (net (code "112") (name "unconnected-(X1H-F-Pad8)") (class "Default")
      (node (ref "X1") (pin "8") (pinfunction "F_8") (pintype "passive"))
    )
    (net (code "113") (name "unconnected-(X1I-F-Pad9)") (class "Default")
      (node (ref "X1") (pin "9") (pinfunction "F_9") (pintype "passive"))
    )
  )
)
